# THAT15xx_DSheet.net
KiCad netlist of a schematic drawn in EAGLE
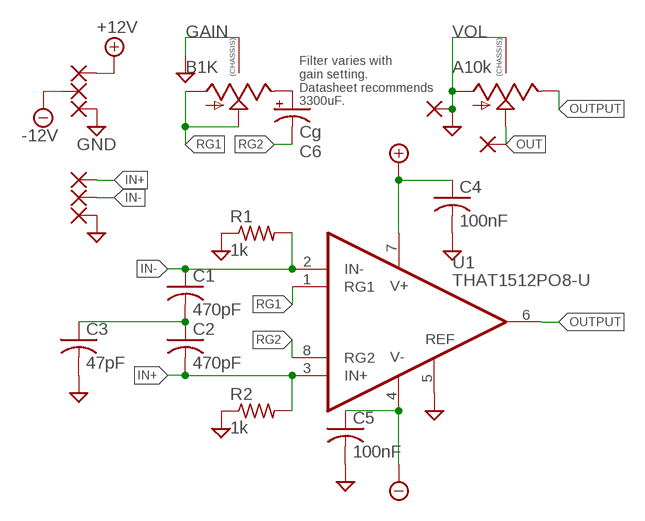
[diagram p0: schematic, sheet 1]

(export (version "E")
  (design (tool "Eeschema 10.0.6"))
  (components
    (comp (ref "C1")
      (value "470pF")
      (footprint "eagle-import:C0805")
      (libsource (lib "eagle-import") (part "C-USC0805"))
    )
    (comp (ref "C2")
      (value "470pF")
      (footprint "eagle-import:C0805")
      (libsource (lib "eagle-import") (part "C-USC0805"))
    )
    (comp (ref "C3")
      (value "47pF")
      (footprint "eagle-import:C0805")
      (libsource (lib "eagle-import") (part "C-USC0805"))
    )
    (comp (ref "C4")
      (value "100nF")
      (footprint "eagle-import:C0805")
      (libsource (lib "eagle-import") (part "C-USC0805"))
    )
    (comp (ref "C5")
      (value "100nF")
      (footprint "eagle-import:C0805")
      (libsource (lib "eagle-import") (part "C-USC0805"))
    )
    (comp (ref "C6")
      (value "Cg")
      (footprint "eagle-import:PAN_C_SMD+THRU")
      (libsource (lib "eagle-import") (part "CAP_SMD+THRUPAN_C"))
    )
    (comp (ref "GAIN")
      (value "B1K")
      (footprint "eagle-import:9MM_SNAP-IN_POT")
      (libsource (lib "eagle-import") (part "9MM_SNAP-IN_POT_CHASSIS"))
    )
    (comp (ref "PAD1")
      (value "WIREPAD1,6/0,9")
      (footprint "eagle-import:1,6_0,9")
      (libsource (lib "eagle-import") (part "WIREPAD1,6/0,9"))
    )
    (comp (ref "PAD2")
      (value "WIREPAD1,6/0,9")
      (footprint "eagle-import:1,6_0,9")
      (libsource (lib "eagle-import") (part "WIREPAD1,6/0,9"))
    )
    (comp (ref "PAD3")
      (value "WIREPAD1,6/0,9")
      (footprint "eagle-import:1,6_0,9")
      (libsource (lib "eagle-import") (part "WIREPAD1,6/0,9"))
    )
    (comp (ref "PAD4")
      (value "WIREPAD1,6/0,9")
      (footprint "eagle-import:1,6_0,9")
      (libsource (lib "eagle-import") (part "WIREPAD1,6/0,9"))
    )
    (comp (ref "PAD5")
      (value "WIREPAD1,6/0,9")
      (footprint "eagle-import:1,6_0,9")
      (libsource (lib "eagle-import") (part "WIREPAD1,6/0,9"))
    )
    (comp (ref "PAD6")
      (value "WIREPAD1,6/0,9")
      (footprint "eagle-import:1,6_0,9")
      (libsource (lib "eagle-import") (part "WIREPAD1,6/0,9"))
    )
    (comp (ref "PAD7")
      (value "WIREPAD1,6/0,9")
      (footprint "eagle-import:1,6_0,9")
      (libsource (lib "eagle-import") (part "WIREPAD1,6/0,9"))
    )
    (comp (ref "PAD8")
      (value "WIREPAD1,6/0,9")
      (footprint "eagle-import:1,6_0,9")
      (libsource (lib "eagle-import") (part "WIREPAD1,6/0,9"))
    )
    (comp (ref "R1")
      (value "1k")
      (footprint "eagle-import:R0805")
      (libsource (lib "eagle-import") (part "R-US_R0805"))
    )
    (comp (ref "R2")
      (value "1k")
      (footprint "eagle-import:R0805")
      (libsource (lib "eagle-import") (part "R-US_R0805"))
    )
    (comp (ref "U1")
      (value "THAT1512PO8-U")
      (footprint "eagle-import:DIL08")
      (libsource (lib "eagle-import") (part "THAT1512PO8-U"))
    )
    (comp (ref "VOL")
      (value "A10k")
      (footprint "eagle-import:9MM_SNAP-IN_POT")
      (libsource (lib "eagle-import") (part "9MM_SNAP-IN_POT_CHASSIS"))
    )
  )
  (nets
    (net (code "1") (name "+12V") (class "Default")
      (node (ref "C4") (pin "1") (pinfunction "1_1") (pintype "passive"))
      (node (ref "PAD3") (pin "1") (pinfunction "P_1") (pintype "passive"))
      (node (ref "U1") (pin "7") (pinfunction "V+_7") (pintype "power_in"))
    )
    (net (code "2") (name "-12V") (class "Default")
      (node (ref "C5") (pin "1") (pinfunction "1_1") (pintype "passive"))
      (node (ref "PAD1") (pin "1") (pinfunction "P_1") (pintype "passive"))
      (node (ref "U1") (pin "4") (pinfunction "V-_4") (pintype "power_in"))
    )
    (net (code "3") (name "GND") (class "Default")
      (node (ref "C3") (pin "2") (pinfunction "2_2") (pintype "passive"))
      (node (ref "C4") (pin "2") (pinfunction "2_2") (pintype "passive"))
      (node (ref "C5") (pin "2") (pinfunction "2_2") (pintype "passive"))
      (node (ref "GAIN") (pin "CHASSIS1") (pinfunction "P$1_CHASSIS1") (pintype "passive"))
      (node (ref "GAIN") (pin "CHASSIS2") (pinfunction "P$1_CHASSIS2") (pintype "passive"))
      (node (ref "PAD2") (pin "1") (pinfunction "P_1") (pintype "passive"))
      (node (ref "PAD6") (pin "1") (pinfunction "P_1") (pintype "passive"))
      (node (ref "PAD7") (pin "1") (pinfunction "P_1") (pintype "passive"))
      (node (ref "R1") (pin "1") (pinfunction "1_1") (pintype "passive"))
      (node (ref "R2") (pin "1") (pinfunction "1_1") (pintype "passive"))
      (node (ref "U1") (pin "5") (pinfunction "REF_5") (pintype "input"))
      (node (ref "VOL") (pin "1") (pinfunction "A_1") (pintype "passive"))
      (node (ref "VOL") (pin "CHASSIS1") (pinfunction "P$1_CHASSIS1") (pintype "passive"))
      (node (ref "VOL") (pin "CHASSIS2") (pinfunction "P$1_CHASSIS2") (pintype "passive"))
    )
    (net (code "4") (name "IN+") (class "Default")
      (node (ref "C2") (pin "2") (pinfunction "2_2") (pintype "passive"))
      (node (ref "PAD4") (pin "1") (pinfunction "P_1") (pintype "passive"))
      (node (ref "R2") (pin "2") (pinfunction "2_2") (pintype "passive"))
      (node (ref "U1") (pin "3") (pinfunction "IN+_3") (pintype "input"))
    )
    (net (code "5") (name "IN-") (class "Default")
      (node (ref "C1") (pin "1") (pinfunction "1_1") (pintype "passive"))
      (node (ref "PAD5") (pin "1") (pinfunction "P_1") (pintype "passive"))
      (node (ref "R1") (pin "2") (pinfunction "2_2") (pintype "passive"))
      (node (ref "U1") (pin "2") (pinfunction "IN-_2") (pintype "input"))
    )
    (net (code "6") (name "Net-(C1-Pad2)") (class "Default")
      (node (ref "C1") (pin "2") (pinfunction "2_2") (pintype "passive"))
      (node (ref "C2") (pin "1") (pinfunction "1_1") (pintype "passive"))
      (node (ref "C3") (pin "1") (pinfunction "1_1") (pintype "passive"))
    )
    (net (code "7") (name "Net-(GAIN-E)") (class "Default")
      (node (ref "C6") (pin "+") (pinfunction "+_+") (pintype "passive"))
      (node (ref "C6") (pin "++") (pinfunction "+_++") (pintype "passive"))
      (node (ref "GAIN") (pin "3") (pinfunction "E_3") (pintype "passive"))
    )
    (net (code "8") (name "OUT") (class "Default")
      (node (ref "PAD8") (pin "1") (pinfunction "P_1") (pintype "passive"))
      (node (ref "VOL") (pin "2") (pinfunction "S_2") (pintype "passive"))
    )
    (net (code "9") (name "OUTPUT") (class "Default")
      (node (ref "U1") (pin "6") (pinfunction "OUT_6") (pintype "output"))
      (node (ref "VOL") (pin "3") (pinfunction "E_3") (pintype "passive"))
    )
    (net (code "10") (name "RG1") (class "Default")
      (node (ref "GAIN") (pin "1") (pinfunction "A_1") (pintype "passive"))
      (node (ref "GAIN") (pin "2") (pinfunction "S_2") (pintype "passive"))
      (node (ref "U1") (pin "1") (pinfunction "RG1_1") (pintype "input"))
    )
    (net (code "11") (name "RG2") (class "Default")
      (node (ref "C6") (pin "-") (pinfunction "-_-") (pintype "passive"))
      (node (ref "C6") (pin "--") (pinfunction "-_--") (pintype "passive"))
      (node (ref "U1") (pin "8") (pinfunction "RG2_8") (pintype "input"))
    )
  )
)
